# Design2d_fertig.net
KiCad netlist of a schematic drawn in EAGLE
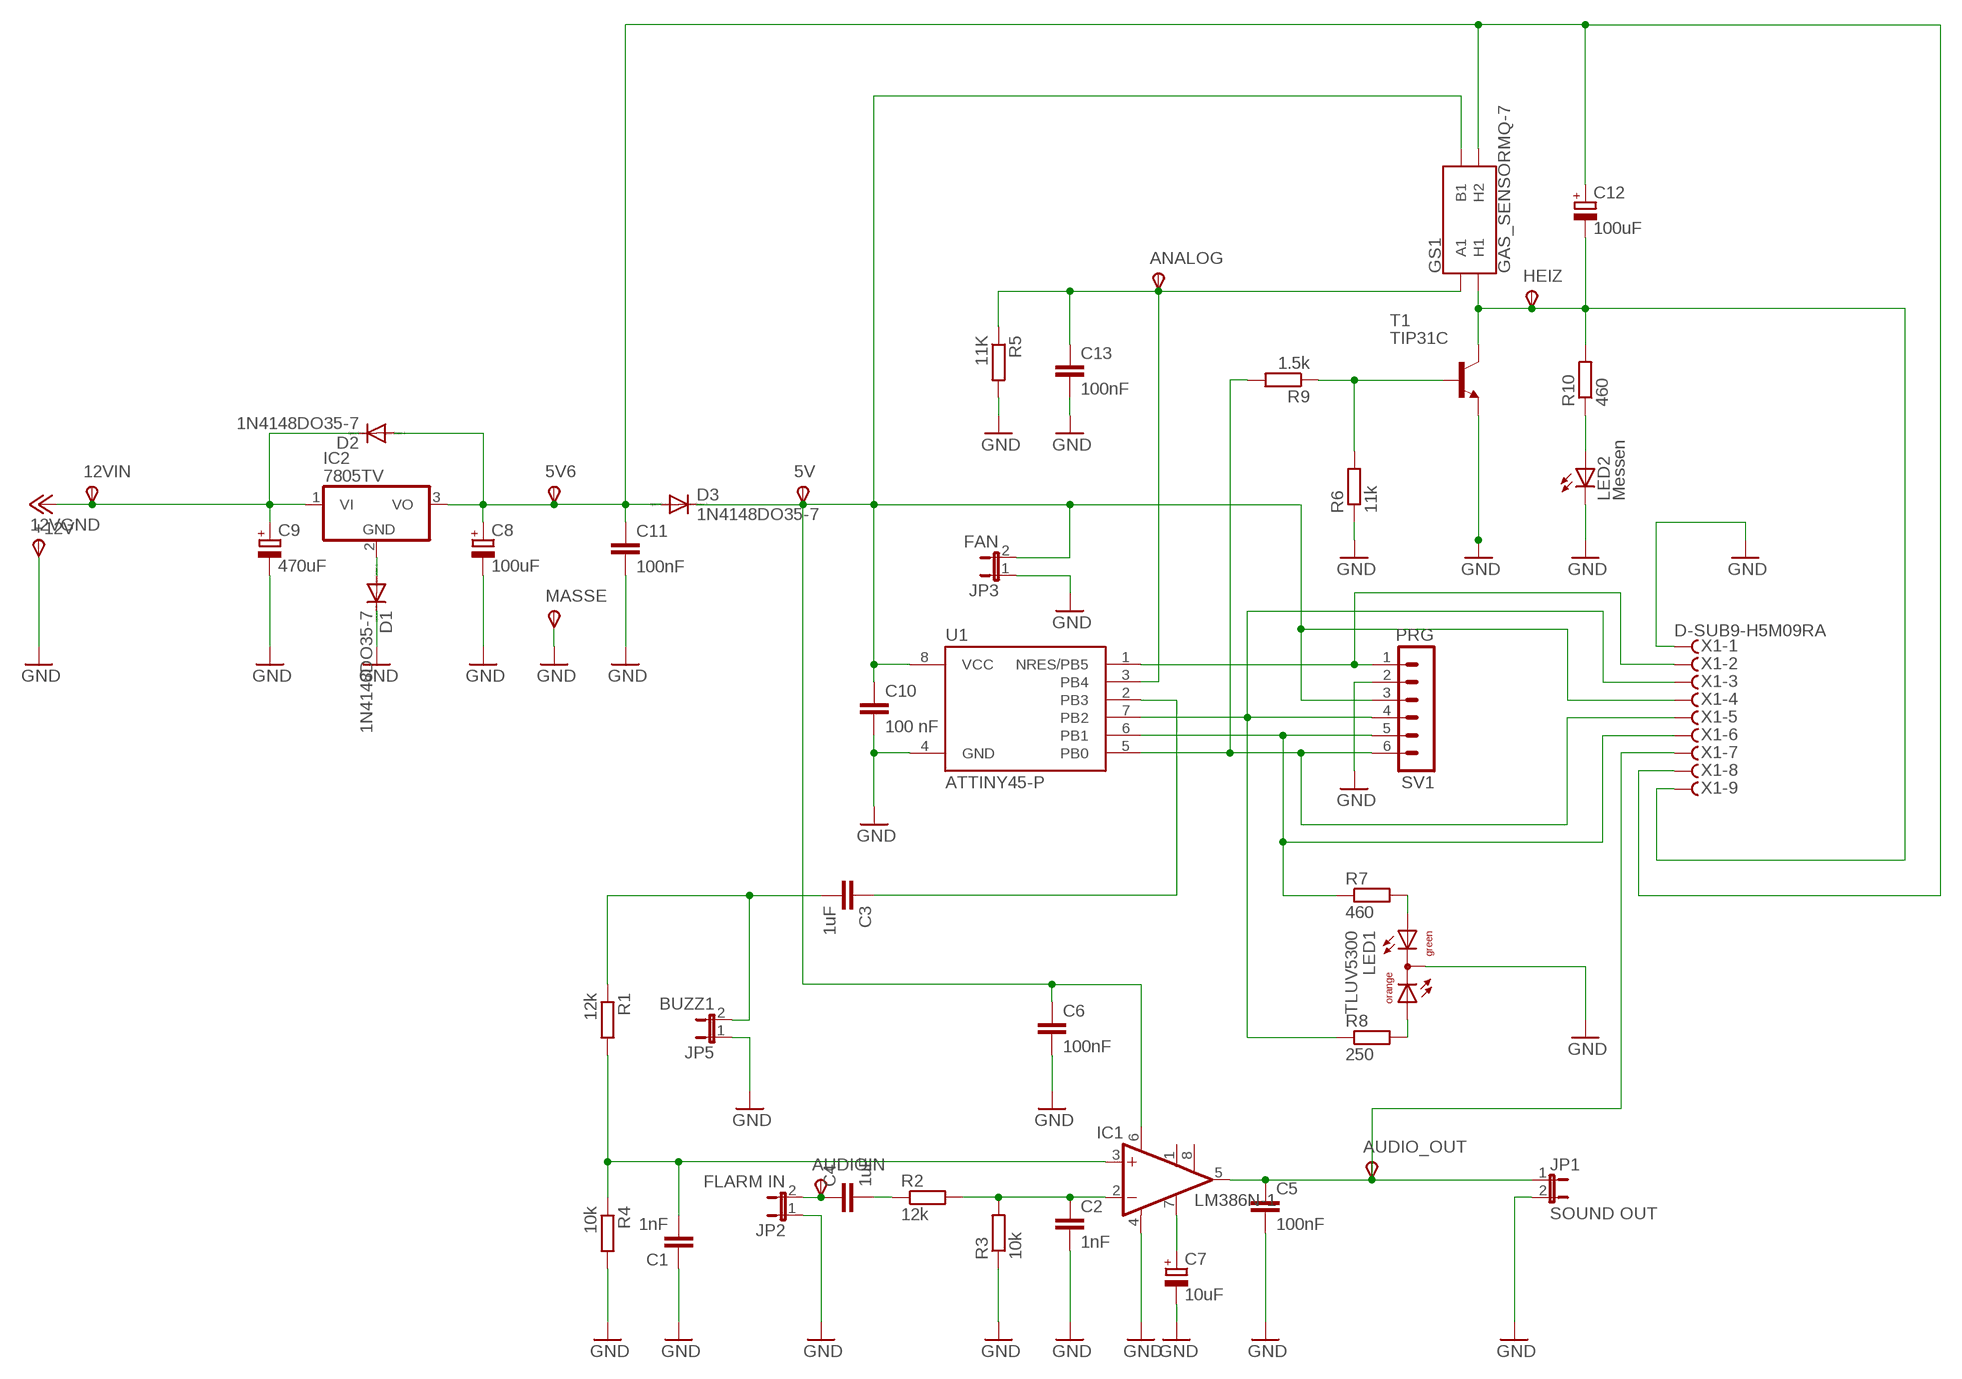
[diagram p0: schematic, sheet 1]

(export (version "E")
  (design (tool "Eeschema 10.0.6"))
  (components
    (comp (ref "5V")
      (value "TPSPAD1-13")
      (footprint "eagle-import:P1-13")
      (libsource (lib "eagle-import") (part "TPSPAD1-13"))
    )
    (comp (ref "5V6")
      (value "TPSPAD1-13")
      (footprint "eagle-import:P1-13")
      (libsource (lib "eagle-import") (part "TPSPAD1-13"))
    )
    (comp (ref "12VGND")
      (value "TPSPAD1-13")
      (footprint "eagle-import:P1-13")
      (libsource (lib "eagle-import") (part "TPSPAD1-13"))
    )
    (comp (ref "12VIN")
      (value "TPSPAD1-13")
      (footprint "eagle-import:P1-13")
      (libsource (lib "eagle-import") (part "TPSPAD1-13"))
    )
    (comp (ref "ANALOG")
      (value "TPSPAD1-13")
      (footprint "eagle-import:P1-13")
      (libsource (lib "eagle-import") (part "TPSPAD1-13"))
    )
    (comp (ref "AUDIOIN")
      (value "TPSPAD1-13")
      (footprint "eagle-import:P1-13")
      (libsource (lib "eagle-import") (part "TPSPAD1-13"))
    )
    (comp (ref "AUDIO_OUT")
      (value "TPSPAD1-13")
      (footprint "eagle-import:P1-13")
      (libsource (lib "eagle-import") (part "TPSPAD1-13"))
    )
    (comp (ref "C1")
      (value "1nF")
      (footprint "eagle-import:C025-030X050")
      (libsource (lib "eagle-import") (part "C-EU025-030X050"))
    )
    (comp (ref "C2")
      (value "1nF")
      (footprint "eagle-import:C025-030X050")
      (libsource (lib "eagle-import") (part "C-EU025-030X050"))
    )
    (comp (ref "C3")
      (value "1uF")
      (footprint "eagle-import:C050-025X075")
      (libsource (lib "eagle-import") (part "C-EU050-025X075"))
    )
    (comp (ref "C4")
      (value "1uF")
      (footprint "eagle-import:C050-025X075")
      (libsource (lib "eagle-import") (part "C-EU050-025X075"))
    )
    (comp (ref "C5")
      (value "100nF")
      (footprint "eagle-import:C050-025X075")
      (libsource (lib "eagle-import") (part "C-EU050-025X075"))
    )
    (comp (ref "C6")
      (value "100nF")
      (footprint "eagle-import:C050-025X075")
      (libsource (lib "eagle-import") (part "C-EU050-025X075"))
    )
    (comp (ref "C7")
      (value "10uF")
      (footprint "eagle-import:E2,5-7")
      (libsource (lib "eagle-import") (part "CPOL-EUE2.5-7"))
    )
    (comp (ref "C8")
      (value "100uF")
      (footprint "eagle-import:E2,5-7")
      (libsource (lib "eagle-import") (part "CPOL-EUE2.5-7"))
    )
    (comp (ref "C9")
      (value "470uF")
      (footprint "eagle-import:E2,5-7")
      (libsource (lib "eagle-import") (part "CPOL-EUE2.5-7"))
    )
    (comp (ref "C10")
      (value "100 nF")
      (footprint "eagle-import:C050-024X044")
      (libsource (lib "eagle-import") (part "C-EU050-024X044"))
    )
    (comp (ref "C11")
      (value "100nF")
      (footprint "eagle-import:C050-025X075")
      (libsource (lib "eagle-import") (part "C-EU050-025X075"))
    )
    (comp (ref "C12")
      (value "100uF")
      (footprint "eagle-import:E2,5-7")
      (libsource (lib "eagle-import") (part "CPOL-EUE2.5-7"))
    )
    (comp (ref "C13")
      (value "100nF")
      (footprint "eagle-import:C050-025X075")
      (libsource (lib "eagle-import") (part "C-EU050-025X075"))
    )
    (comp (ref "D1")
      (value "1N4148DO35-7")
      (footprint "eagle-import:DO35-7")
      (libsource (lib "eagle-import") (part "1N4148DO35-7"))
    )
    (comp (ref "D2")
      (value "1N4148DO35-7")
      (footprint "eagle-import:DO35-7")
      (libsource (lib "eagle-import") (part "1N4148DO35-7"))
    )
    (comp (ref "D3")
      (value "1N4148DO35-7")
      (footprint "eagle-import:DO35-7")
      (libsource (lib "eagle-import") (part "1N4148DO35-7"))
    )
    (comp (ref "GS1")
      (value "GAS_SENSORMQ-7")
      (footprint "eagle-import:GAS_SENSOR")
      (libsource (lib "eagle-import") (part "GAS_SENSORMQ-7"))
    )
    (comp (ref "HEIZ")
      (value "TPSPAD1-13")
      (footprint "eagle-import:P1-13")
      (libsource (lib "eagle-import") (part "TPSPAD1-13"))
    )
    (comp (ref "IC1")
      (value "LM386N-1")
      (footprint "eagle-import:DIL08")
      (libsource (lib "eagle-import") (part "LM386?-N1"))
    )
    (comp (ref "IC2")
      (value "7805TV")
      (footprint "eagle-import:TO220V")
      (libsource (lib "eagle-import") (part "78TV05"))
    )
    (comp (ref "JP1")
      (value "SOUND OUT")
      (footprint "eagle-import:JP1")
      (libsource (lib "eagle-import") (part "JP1E"))
    )
    (comp (ref "JP2")
      (value "FLARM IN")
      (footprint "eagle-import:JP1")
      (libsource (lib "eagle-import") (part "JP1E"))
    )
    (comp (ref "JP3")
      (value "FAN")
      (footprint "eagle-import:JP1")
      (libsource (lib "eagle-import") (part "JP1E"))
    )
    (comp (ref "JP5")
      (value "BUZZ1")
      (footprint "eagle-import:JP1")
      (libsource (lib "eagle-import") (part "JP1E"))
    )
    (comp (ref "LED1")
      (value "TLUV5300")
      (footprint "eagle-import:TLUV5300")
      (libsource (lib "eagle-import") (part "TLUV5300"))
    )
    (comp (ref "LED2")
      (value "Messen")
      (footprint "eagle-import:LED3MM")
      (libsource (lib "eagle-import") (part "LED3MM"))
    )
    (comp (ref "MASSE")
      (value "TPSPAD1-13")
      (footprint "eagle-import:P1-13")
      (libsource (lib "eagle-import") (part "TPSPAD1-13"))
    )
    (comp (ref "R1")
      (value "12k")
      (footprint "eagle-import:0207_10")
      (libsource (lib "eagle-import") (part "R-EU_0207/10"))
    )
    (comp (ref "R2")
      (value "12k")
      (footprint "eagle-import:0207_10")
      (libsource (lib "eagle-import") (part "R-EU_0207/10"))
    )
    (comp (ref "R3")
      (value "10k")
      (footprint "eagle-import:0207_10")
      (libsource (lib "eagle-import") (part "R-EU_0207/10"))
    )
    (comp (ref "R4")
      (value "10k")
      (footprint "eagle-import:0207_10")
      (libsource (lib "eagle-import") (part "R-EU_0207/10"))
    )
    (comp (ref "R5")
      (value "11K")
      (footprint "eagle-import:0207_10")
      (libsource (lib "eagle-import") (part "R-EU_0207/10"))
    )
    (comp (ref "R6")
      (value "11k")
      (footprint "eagle-import:0207_10")
      (libsource (lib "eagle-import") (part "R-EU_0207/10"))
    )
    (comp (ref "R7")
      (value "460")
      (footprint "eagle-import:0207_10")
      (libsource (lib "eagle-import") (part "R-EU_0207/10"))
    )
    (comp (ref "R8")
      (value "250")
      (footprint "eagle-import:0207_10")
      (libsource (lib "eagle-import") (part "R-EU_0207/10"))
    )
    (comp (ref "R9")
      (value "1.5k")
      (footprint "eagle-import:0207_10")
      (libsource (lib "eagle-import") (part "R-EU_0207/10"))
    )
    (comp (ref "R10")
      (value "460")
      (footprint "eagle-import:0207_10")
      (libsource (lib "eagle-import") (part "R-EU_0207/10"))
    )
    (comp (ref "SV1")
      (value "PRG")
      (footprint "eagle-import:MA06-1")
      (libsource (lib "eagle-import") (part "MA06-1"))
    )
    (comp (ref "T1")
      (value "TIP31C")
      (footprint "eagle-import:TO220V")
      (libsource (lib "eagle-import") (part "-NPN-TO220V"))
    )
    (comp (ref "U1")
      (value "ATTINY45-P")
      (footprint "eagle-import:PDIP08_300MIL")
      (libsource (lib "eagle-import") (part "ATTINY45P-"))
    )
    (comp (ref "X1")
      (value "D-SUB9-H5M09RA")
      (footprint "eagle-import:H5M09RA")
      (libsource (lib "eagle-import") (part "D-SUB9-H5M09RA"))
    )
  )
  (nets
    (net (code "1") (name "+12V") (class "Default")
      (node (ref "12VIN") (pin "TP") (pinfunction "PP_TP") (pintype "input"))
      (node (ref "C9") (pin "+") (pinfunction "+_+") (pintype "passive"))
      (node (ref "D2") (pin "C") (pinfunction "C_C") (pintype "passive"))
      (node (ref "IC2") (pin "1") (pinfunction "VI_1") (pintype "input"))
    )
    (net (code "2") (name "GND") (class "Default")
      (node (ref "12VGND") (pin "TP") (pinfunction "PP_TP") (pintype "input"))
      (node (ref "C1") (pin "1") (pinfunction "1_1") (pintype "passive"))
      (node (ref "C10") (pin "2") (pinfunction "2_2") (pintype "passive"))
      (node (ref "C11") (pin "2") (pinfunction "2_2") (pintype "passive"))
      (node (ref "C13") (pin "2") (pinfunction "2_2") (pintype "passive"))
      (node (ref "C2") (pin "2") (pinfunction "2_2") (pintype "passive"))
      (node (ref "C5") (pin "2") (pinfunction "2_2") (pintype "passive"))
      (node (ref "C6") (pin "2") (pinfunction "2_2") (pintype "passive"))
      (node (ref "C7") (pin "-") (pinfunction "-_-") (pintype "passive"))
      (node (ref "C8") (pin "-") (pinfunction "-_-") (pintype "passive"))
      (node (ref "C9") (pin "-") (pinfunction "-_-") (pintype "passive"))
      (node (ref "D1") (pin "C") (pinfunction "C_C") (pintype "passive"))
      (node (ref "IC1") (pin "4") (pinfunction "GND_4") (pintype "power_in"))
      (node (ref "JP1") (pin "2") (pinfunction "2_2") (pintype "passive"))
      (node (ref "JP2") (pin "1") (pinfunction "1_1") (pintype "passive"))
      (node (ref "JP3") (pin "1") (pinfunction "1_1") (pintype "passive"))
      (node (ref "JP5") (pin "1") (pinfunction "1_1") (pintype "passive"))
      (node (ref "LED1") (pin "CC") (pinfunction "CC_CC") (pintype "passive"))
      (node (ref "LED2") (pin "K") (pinfunction "C_K") (pintype "passive"))
      (node (ref "MASSE") (pin "TP") (pinfunction "PP_TP") (pintype "input"))
      (node (ref "R3") (pin "1") (pinfunction "1_1") (pintype "passive"))
      (node (ref "R4") (pin "2") (pinfunction "2_2") (pintype "passive"))
      (node (ref "R5") (pin "2") (pinfunction "2_2") (pintype "passive"))
      (node (ref "R6") (pin "1") (pinfunction "1_1") (pintype "passive"))
      (node (ref "SV1") (pin "2") (pinfunction "2_2") (pintype "passive"))
      (node (ref "T1") (pin "3") (pinfunction "E_3") (pintype "passive"))
      (node (ref "U1") (pin "4") (pinfunction "GND_4") (pintype "power_in"))
      (node (ref "X1") (pin "1") (pinfunction "F_1") (pintype "passive"))
    )
    (net (code "3") (name "Net-(5V-PP)") (class "Default")
      (node (ref "5V") (pin "TP") (pinfunction "PP_TP") (pintype "input"))
      (node (ref "C10") (pin "1") (pinfunction "1_1") (pintype "passive"))
      (node (ref "C6") (pin "1") (pinfunction "1_1") (pintype "passive"))
      (node (ref "D3") (pin "C") (pinfunction "C_C") (pintype "passive"))
      (node (ref "GS1") (pin "B1") (pinfunction "B1_B1") (pintype "bidirectional"))
      (node (ref "IC1") (pin "6") (pinfunction "VS_6") (pintype "power_in"))
      (node (ref "JP3") (pin "2") (pinfunction "2_2") (pintype "passive"))
      (node (ref "SV1") (pin "3") (pinfunction "3_3") (pintype "passive"))
      (node (ref "U1") (pin "8") (pinfunction "VCC_8") (pintype "power_in"))
      (node (ref "X1") (pin "4") (pinfunction "F_4") (pintype "passive"))
    )
    (net (code "4") (name "Net-(5V6-PP)") (class "Default")
      (node (ref "5V6") (pin "TP") (pinfunction "PP_TP") (pintype "input"))
      (node (ref "C11") (pin "1") (pinfunction "1_1") (pintype "passive"))
      (node (ref "C12") (pin "+") (pinfunction "+_+") (pintype "passive"))
      (node (ref "C8") (pin "+") (pinfunction "+_+") (pintype "passive"))
      (node (ref "D2") (pin "A") (pinfunction "A_A") (pintype "passive"))
      (node (ref "D3") (pin "A") (pinfunction "A_A") (pintype "passive"))
      (node (ref "GS1") (pin "HB") (pinfunction "H2_HB") (pintype "bidirectional"))
      (node (ref "IC2") (pin "3") (pinfunction "VO_3") (pintype "passive"))
      (node (ref "X1") (pin "8") (pinfunction "F_8") (pintype "passive"))
    )
    (net (code "5") (name "Net-(ANALOG-PP)") (class "Default")
      (node (ref "ANALOG") (pin "TP") (pinfunction "PP_TP") (pintype "input"))
      (node (ref "C13") (pin "1") (pinfunction "1_1") (pintype "passive"))
      (node (ref "GS1") (pin "A1") (pinfunction "A1_A1") (pintype "bidirectional"))
      (node (ref "R5") (pin "1") (pinfunction "1_1") (pintype "passive"))
      (node (ref "U1") (pin "3") (pinfunction "PB4_3") (pintype "bidirectional"))
    )
    (net (code "6") (name "Net-(AUDIOIN-PP)") (class "Default")
      (node (ref "AUDIOIN") (pin "TP") (pinfunction "PP_TP") (pintype "input"))
      (node (ref "C4") (pin "1") (pinfunction "1_1") (pintype "passive"))
      (node (ref "JP2") (pin "2") (pinfunction "2_2") (pintype "passive"))
    )
    (net (code "7") (name "Net-(AUDIO_OUT-PP)") (class "Default")
      (node (ref "AUDIO_OUT") (pin "TP") (pinfunction "PP_TP") (pintype "input"))
      (node (ref "C5") (pin "1") (pinfunction "1_1") (pintype "passive"))
      (node (ref "IC1") (pin "5") (pinfunction "OUT_5") (pintype "output"))
      (node (ref "JP1") (pin "1") (pinfunction "1_1") (pintype "passive"))
      (node (ref "X1") (pin "7") (pinfunction "F_7") (pintype "passive"))
    )
    (net (code "8") (name "Net-(C3-Pad2)") (class "Default")
      (node (ref "C3") (pin "2") (pinfunction "2_2") (pintype "passive"))
      (node (ref "JP5") (pin "2") (pinfunction "2_2") (pintype "passive"))
      (node (ref "R1") (pin "1") (pinfunction "1_1") (pintype "passive"))
    )
    (net (code "9") (name "Net-(C4-Pad2)") (class "Default")
      (node (ref "C4") (pin "2") (pinfunction "2_2") (pintype "passive"))
      (node (ref "R2") (pin "1") (pinfunction "1_1") (pintype "passive"))
    )
    (net (code "10") (name "Net-(GS1-H1)") (class "Default")
      (node (ref "C12") (pin "-") (pinfunction "-_-") (pintype "passive"))
      (node (ref "GS1") (pin "HA") (pinfunction "H1_HA") (pintype "bidirectional"))
      (node (ref "HEIZ") (pin "TP") (pinfunction "PP_TP") (pintype "input"))
      (node (ref "R10") (pin "2") (pinfunction "2_2") (pintype "passive"))
      (node (ref "T1") (pin "2") (pinfunction "C_2") (pintype "passive"))
      (node (ref "X1") (pin "9") (pinfunction "F_9") (pintype "passive"))
    )
    (net (code "11") (name "Net-(IC1-+IN)") (class "Default")
      (node (ref "C1") (pin "2") (pinfunction "2_2") (pintype "passive"))
      (node (ref "IC1") (pin "3") (pinfunction "+IN_3") (pintype "input"))
      (node (ref "R1") (pin "2") (pinfunction "2_2") (pintype "passive"))
      (node (ref "R4") (pin "1") (pinfunction "1_1") (pintype "passive"))
    )
    (net (code "12") (name "Net-(IC1--IN)") (class "Default")
      (node (ref "C2") (pin "1") (pinfunction "1_1") (pintype "passive"))
      (node (ref "IC1") (pin "2") (pinfunction "-IN_2") (pintype "input"))
      (node (ref "R2") (pin "2") (pinfunction "2_2") (pintype "passive"))
      (node (ref "R3") (pin "2") (pinfunction "2_2") (pintype "passive"))
    )
    (net (code "13") (name "Net-(IC1-BYPASS)") (class "Default")
      (node (ref "C7") (pin "+") (pinfunction "+_+") (pintype "passive"))
      (node (ref "IC1") (pin "7") (pinfunction "BYPASS_7") (pintype "passive"))
    )
    (net (code "14") (name "Net-(IC2-GND)") (class "Default")
      (node (ref "D1") (pin "A") (pinfunction "A_A") (pintype "passive"))
      (node (ref "IC2") (pin "2") (pinfunction "GND_2") (pintype "passive"))
    )
    (net (code "15") (name "Net-(LED1-PadAG)") (class "Default")
      (node (ref "LED1") (pin "AG") (pinfunction "AG_AG") (pintype "passive"))
      (node (ref "R7") (pin "2") (pinfunction "2_2") (pintype "passive"))
    )
    (net (code "16") (name "Net-(LED1-PadAO)") (class "Default")
      (node (ref "LED1") (pin "AO") (pinfunction "AO_AO") (pintype "passive"))
      (node (ref "R8") (pin "2") (pinfunction "2_2") (pintype "passive"))
    )
    (net (code "17") (name "Net-(LED2-PadA)") (class "Default")
      (node (ref "LED2") (pin "A") (pinfunction "A_A") (pintype "passive"))
      (node (ref "R10") (pin "1") (pinfunction "1_1") (pintype "passive"))
    )
    (net (code "18") (name "Net-(T1-B)") (class "Default")
      (node (ref "R6") (pin "2") (pinfunction "2_2") (pintype "passive"))
      (node (ref "R9") (pin "1") (pinfunction "1_1") (pintype "passive"))
      (node (ref "T1") (pin "1") (pinfunction "B_1") (pintype "passive"))
    )
    (net (code "19") (name "Net-(U1-NRES{slash}PB5)") (class "Default")
      (node (ref "SV1") (pin "1") (pinfunction "1_1") (pintype "passive"))
      (node (ref "U1") (pin "1") (pinfunction "NRES/PB5_1") (pintype "bidirectional"))
      (node (ref "X1") (pin "2") (pinfunction "F_2") (pintype "passive"))
    )
    (net (code "20") (name "Net-(U1-PB0)") (class "Default")
      (node (ref "R9") (pin "2") (pinfunction "2_2") (pintype "passive"))
      (node (ref "SV1") (pin "6") (pinfunction "6_6") (pintype "passive"))
      (node (ref "U1") (pin "5") (pinfunction "PB0_5") (pintype "bidirectional"))
      (node (ref "X1") (pin "5") (pinfunction "F_5") (pintype "passive"))
    )
    (net (code "21") (name "Net-(U1-PB1)") (class "Default")
      (node (ref "R7") (pin "1") (pinfunction "1_1") (pintype "passive"))
      (node (ref "SV1") (pin "5") (pinfunction "5_5") (pintype "passive"))
      (node (ref "U1") (pin "6") (pinfunction "PB1_6") (pintype "bidirectional"))
      (node (ref "X1") (pin "6") (pinfunction "F_6") (pintype "passive"))
    )
    (net (code "22") (name "Net-(U1-PB2)") (class "Default")
      (node (ref "R8") (pin "1") (pinfunction "1_1") (pintype "passive"))
      (node (ref "SV1") (pin "4") (pinfunction "4_4") (pintype "passive"))
      (node (ref "U1") (pin "7") (pinfunction "PB2_7") (pintype "bidirectional"))
      (node (ref "X1") (pin "3") (pinfunction "F_3") (pintype "passive"))
    )
    (net (code "23") (name "Net-(U1-PB3)") (class "Default")
      (node (ref "C3") (pin "1") (pinfunction "1_1") (pintype "passive"))
      (node (ref "U1") (pin "2") (pinfunction "PB3_2") (pintype "bidirectional"))
    )
    (net (code "24") (name "unconnected-(IC1-GAIN-Pad1)") (class "Default")
      (node (ref "IC1") (pin "1") (pinfunction "GAIN_1") (pintype "passive"))
    )
    (net (code "25") (name "unconnected-(IC1-GAIN-Pad8)") (class "Default")
      (node (ref "IC1") (pin "8") (pinfunction "GAIN_8") (pintype "passive"))
    )
  )
)
